# Voltage_Ref.net
KiCad netlist of a schematic drawn in Altium Designer
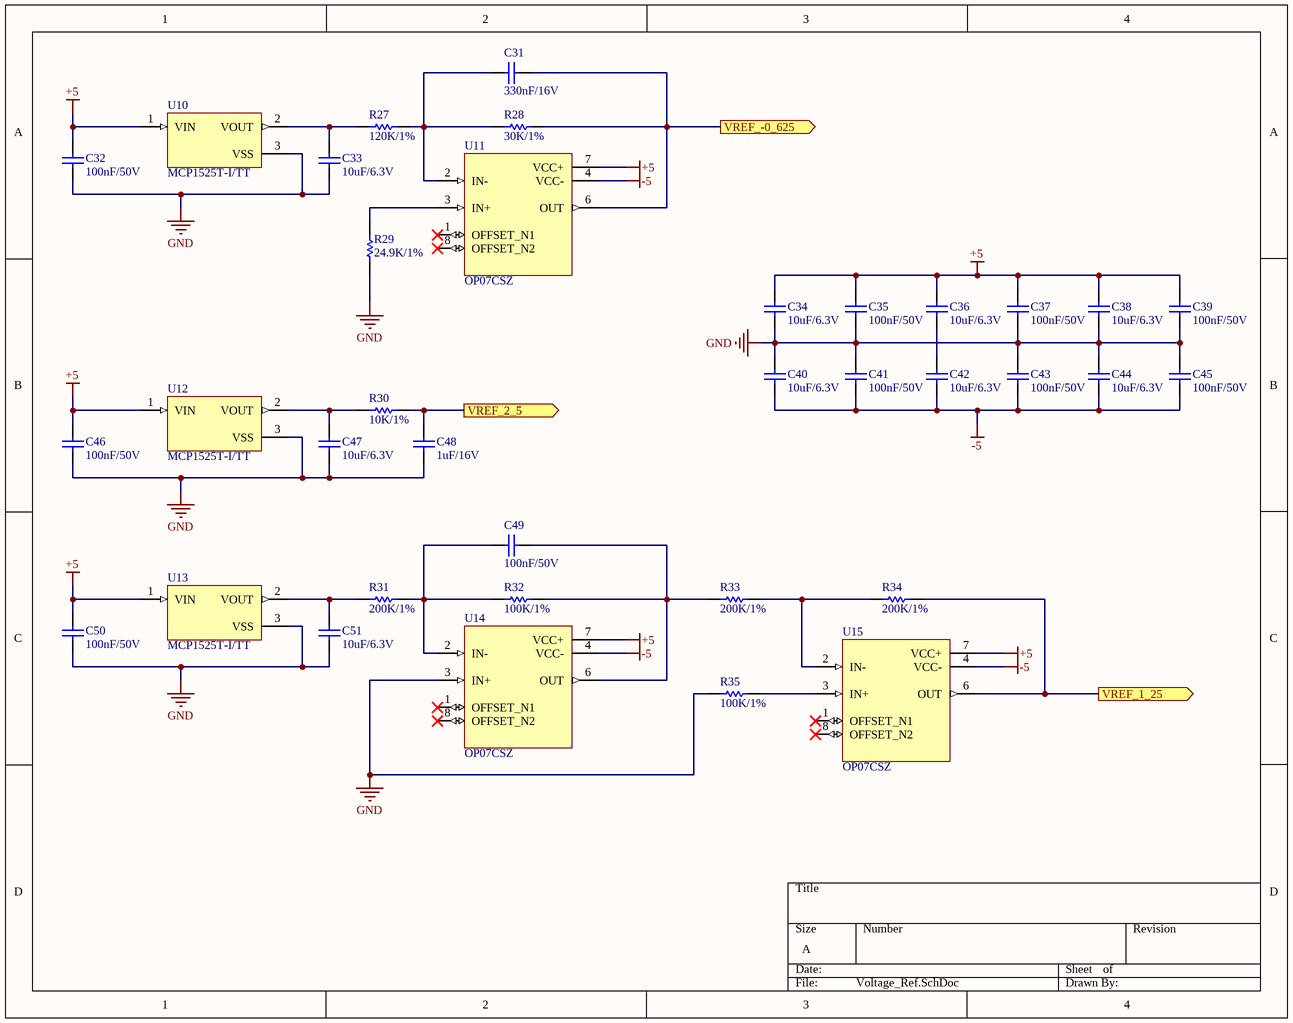
[diagram p0: Voltage_Ref.SchDoc]

(export (version "E")
  (design (tool "Eeschema 10.0.6"))
  (components
    (comp (ref "C31")
      (value "330nF/16V")
      (footprint "CAP_0805")
      (libsource (lib "Iot_Flatform_lib_PTT") (part "Capacitor"))
    )
    (comp (ref "C32")
      (value "100nF/50V")
      (footprint "CAP_0805")
      (libsource (lib "Iot_Flatform_lib_PTT") (part "Capacitor"))
    )
    (comp (ref "C33")
      (value "10uF/6.3V")
      (footprint "CAP_0805")
      (libsource (lib "Iot_Flatform_lib_PTT") (part "Capacitor"))
    )
    (comp (ref "C34")
      (value "10uF/6.3V")
      (footprint "CAP_0805")
      (libsource (lib "Iot_Flatform_lib_PTT") (part "Capacitor"))
    )
    (comp (ref "C35")
      (value "100nF/50V")
      (footprint "CAP_0805")
      (libsource (lib "Iot_Flatform_lib_PTT") (part "Capacitor"))
    )
    (comp (ref "C36")
      (value "10uF/6.3V")
      (footprint "CAP_0805")
      (libsource (lib "Iot_Flatform_lib_PTT") (part "Capacitor"))
    )
    (comp (ref "C37")
      (value "100nF/50V")
      (footprint "CAP_0805")
      (libsource (lib "Iot_Flatform_lib_PTT") (part "Capacitor"))
    )
    (comp (ref "C38")
      (value "10uF/6.3V")
      (footprint "CAP_0805")
      (libsource (lib "Iot_Flatform_lib_PTT") (part "Capacitor"))
    )
    (comp (ref "C39")
      (value "100nF/50V")
      (footprint "CAP_0805")
      (libsource (lib "Iot_Flatform_lib_PTT") (part "Capacitor"))
    )
    (comp (ref "C40")
      (value "10uF/6.3V")
      (footprint "CAP_0805")
      (libsource (lib "Iot_Flatform_lib_PTT") (part "Capacitor"))
    )
    (comp (ref "C41")
      (value "100nF/50V")
      (footprint "CAP_0805")
      (libsource (lib "Iot_Flatform_lib_PTT") (part "Capacitor"))
    )
    (comp (ref "C42")
      (value "10uF/6.3V")
      (footprint "CAP_0805")
      (libsource (lib "Iot_Flatform_lib_PTT") (part "Capacitor"))
    )
    (comp (ref "C43")
      (value "100nF/50V")
      (footprint "CAP_0805")
      (libsource (lib "Iot_Flatform_lib_PTT") (part "Capacitor"))
    )
    (comp (ref "C44")
      (value "10uF/6.3V")
      (footprint "CAP_0805")
      (libsource (lib "Iot_Flatform_lib_PTT") (part "Capacitor"))
    )
    (comp (ref "C45")
      (value "100nF/50V")
      (footprint "CAP_0805")
      (libsource (lib "Iot_Flatform_lib_PTT") (part "Capacitor"))
    )
    (comp (ref "C46")
      (value "100nF/50V")
      (footprint "CAP_0805")
      (libsource (lib "Iot_Flatform_lib_PTT") (part "Capacitor"))
    )
    (comp (ref "C47")
      (value "10uF/6.3V")
      (footprint "CAP_0805")
      (libsource (lib "Iot_Flatform_lib_PTT") (part "Capacitor"))
    )
    (comp (ref "C48")
      (value "1uF/16V")
      (footprint "CAP_0805")
      (libsource (lib "Iot_Flatform_lib_PTT") (part "Capacitor"))
    )
    (comp (ref "C49")
      (value "100nF/50V")
      (footprint "CAP_0805")
      (libsource (lib "Iot_Flatform_lib_PTT") (part "Capacitor"))
    )
    (comp (ref "C50")
      (value "100nF/50V")
      (footprint "CAP_0805")
      (libsource (lib "Iot_Flatform_lib_PTT") (part "Capacitor"))
    )
    (comp (ref "C51")
      (value "10uF/6.3V")
      (footprint "CAP_0805")
      (libsource (lib "Iot_Flatform_lib_PTT") (part "Capacitor"))
    )
    (comp (ref "R27")
      (value "120K/1%")
      (footprint "RES_0805")
      (libsource (lib "Iot_Flatform_lib_PTT") (part "Resistor"))
    )
    (comp (ref "R28")
      (value "30K/1%")
      (footprint "RES_0805")
      (libsource (lib "Iot_Flatform_lib_PTT") (part "Resistor"))
    )
    (comp (ref "R29")
      (value "24.9K/1%")
      (footprint "RES_0805")
      (libsource (lib "Iot_Flatform_lib_PTT") (part "Resistor"))
    )
    (comp (ref "R30")
      (value "10K/1%")
      (footprint "RES_0805")
      (libsource (lib "Iot_Flatform_lib_PTT") (part "Resistor"))
    )
    (comp (ref "R31")
      (value "200K/1%")
      (footprint "RES_0805")
      (libsource (lib "Iot_Flatform_lib_PTT") (part "Resistor"))
    )
    (comp (ref "R32")
      (value "100K/1%")
      (footprint "RES_0805")
      (libsource (lib "Iot_Flatform_lib_PTT") (part "Resistor"))
    )
    (comp (ref "R33")
      (value "200K/1%")
      (footprint "RES_0805")
      (libsource (lib "Iot_Flatform_lib_PTT") (part "Resistor"))
    )
    (comp (ref "R34")
      (value "200K/1%")
      (footprint "RES_0805")
      (libsource (lib "Iot_Flatform_lib_PTT") (part "Resistor"))
    )
    (comp (ref "R35")
      (value "100K/1%")
      (footprint "RES_0805")
      (libsource (lib "Iot_Flatform_lib_PTT") (part "Resistor"))
    )
    (comp (ref "U10")
      (value "MCP1525T-I/TT")
      (footprint "SOT95P237X112-3N")
      (description "Series Voltage Reference IC Â±1% SOT-23-3")
      (libsource (lib "Iot_Flatform_lib_PTT") (part "MCP1525T-I/TT"))
    )
    (comp (ref "U11")
      (value "OP07CSZ")
      (footprint "SOIC127P600X175-8N")
      (description "Low-Offset Voltage Operational Amplifier")
      (libsource (lib "Iot_Flatform_lib_PTT") (part "OP07CSZ"))
    )
    (comp (ref "U12")
      (value "MCP1525T-I/TT")
      (footprint "SOT95P237X112-3N")
      (description "Series Voltage Reference IC Â±1% SOT-23-3")
      (libsource (lib "Iot_Flatform_lib_PTT") (part "MCP1525T-I/TT"))
    )
    (comp (ref "U13")
      (value "MCP1525T-I/TT")
      (footprint "SOT95P237X112-3N")
      (description "Series Voltage Reference IC Â±1% SOT-23-3")
      (libsource (lib "Iot_Flatform_lib_PTT") (part "MCP1525T-I/TT"))
    )
    (comp (ref "U14")
      (value "OP07CSZ")
      (footprint "SOIC127P600X175-8N")
      (description "Low-Offset Voltage Operational Amplifier")
      (libsource (lib "Iot_Flatform_lib_PTT") (part "OP07CSZ"))
    )
    (comp (ref "U15")
      (value "OP07CSZ")
      (footprint "SOIC127P600X175-8N")
      (description "Low-Offset Voltage Operational Amplifier")
      (libsource (lib "Iot_Flatform_lib_PTT") (part "OP07CSZ"))
    )
  )
  (nets
    (net (code "1") (name "+5") (class "Default")
      (node (ref "C32") (pin "2") (pinfunction "2_2") (pintype "passive"))
      (node (ref "C34") (pin "2") (pinfunction "2_2") (pintype "passive"))
      (node (ref "C35") (pin "2") (pinfunction "2_2") (pintype "passive"))
      (node (ref "C36") (pin "2") (pinfunction "2_2") (pintype "passive"))
      (node (ref "C37") (pin "2") (pinfunction "2_2") (pintype "passive"))
      (node (ref "C38") (pin "2") (pinfunction "2_2") (pintype "passive"))
      (node (ref "C39") (pin "2") (pinfunction "2_2") (pintype "passive"))
      (node (ref "C46") (pin "2") (pinfunction "2_2") (pintype "passive"))
      (node (ref "C50") (pin "2") (pinfunction "2_2") (pintype "passive"))
      (node (ref "U10") (pin "1") (pinfunction "VIN_1") (pintype "input"))
      (node (ref "U11") (pin "7") (pinfunction "VCC+_7") (pintype "power_in"))
      (node (ref "U12") (pin "1") (pinfunction "VIN_1") (pintype "input"))
      (node (ref "U13") (pin "1") (pinfunction "VIN_1") (pintype "input"))
      (node (ref "U14") (pin "7") (pinfunction "VCC+_7") (pintype "power_in"))
      (node (ref "U15") (pin "7") (pinfunction "VCC+_7") (pintype "power_in"))
    )
    (net (code "2") (name "-5") (class "Default")
      (node (ref "C40") (pin "1") (pinfunction "1_1") (pintype "passive"))
      (node (ref "C41") (pin "1") (pinfunction "1_1") (pintype "passive"))
      (node (ref "C42") (pin "1") (pinfunction "1_1") (pintype "passive"))
      (node (ref "C43") (pin "1") (pinfunction "1_1") (pintype "passive"))
      (node (ref "C44") (pin "1") (pinfunction "1_1") (pintype "passive"))
      (node (ref "C45") (pin "1") (pinfunction "1_1") (pintype "passive"))
      (node (ref "U11") (pin "4") (pinfunction "VCC-_4") (pintype "power_in"))
      (node (ref "U14") (pin "4") (pinfunction "VCC-_4") (pintype "power_in"))
      (node (ref "U15") (pin "4") (pinfunction "VCC-_4") (pintype "power_in"))
    )
    (net (code "3") (name "/VREF_-0_625") (class "Default")
      (node (ref "C31") (pin "1") (pinfunction "1_1") (pintype "passive"))
      (node (ref "R28") (pin "2") (pinfunction "2_2") (pintype "passive"))
      (node (ref "U11") (pin "6") (pinfunction "OUT_6") (pintype "output"))
    )
    (net (code "4") (name "/VREF_1_25") (class "Default")
      (node (ref "R34") (pin "2") (pinfunction "2_2") (pintype "passive"))
      (node (ref "U15") (pin "6") (pinfunction "OUT_6") (pintype "output"))
    )
    (net (code "5") (name "/VREF_2_5") (class "Default")
      (node (ref "C48") (pin "2") (pinfunction "2_2") (pintype "passive"))
      (node (ref "R30") (pin "1") (pinfunction "1_1") (pintype "passive"))
    )
    (net (code "6") (name "GND") (class "Default")
      (node (ref "C32") (pin "1") (pinfunction "1_1") (pintype "passive"))
      (node (ref "C33") (pin "1") (pinfunction "1_1") (pintype "passive"))
      (node (ref "C34") (pin "1") (pinfunction "1_1") (pintype "passive"))
      (node (ref "C35") (pin "1") (pinfunction "1_1") (pintype "passive"))
      (node (ref "C37") (pin "1") (pinfunction "1_1") (pintype "passive"))
      (node (ref "C38") (pin "1") (pinfunction "1_1") (pintype "passive"))
      (node (ref "C39") (pin "1") (pinfunction "1_1") (pintype "passive"))
      (node (ref "C40") (pin "2") (pinfunction "2_2") (pintype "passive"))
      (node (ref "C41") (pin "2") (pinfunction "2_2") (pintype "passive"))
      (node (ref "C43") (pin "2") (pinfunction "2_2") (pintype "passive"))
      (node (ref "C44") (pin "2") (pinfunction "2_2") (pintype "passive"))
      (node (ref "C45") (pin "2") (pinfunction "2_2") (pintype "passive"))
      (node (ref "C46") (pin "1") (pinfunction "1_1") (pintype "passive"))
      (node (ref "C47") (pin "1") (pinfunction "1_1") (pintype "passive"))
      (node (ref "C48") (pin "1") (pinfunction "1_1") (pintype "passive"))
      (node (ref "C50") (pin "1") (pinfunction "1_1") (pintype "passive"))
      (node (ref "C51") (pin "1") (pinfunction "1_1") (pintype "passive"))
      (node (ref "R29") (pin "1") (pinfunction "1_1") (pintype "passive"))
      (node (ref "R35") (pin "1") (pinfunction "1_1") (pintype "passive"))
      (node (ref "U10") (pin "3") (pinfunction "VSS_3") (pintype "power_in"))
      (node (ref "U12") (pin "3") (pinfunction "VSS_3") (pintype "power_in"))
      (node (ref "U13") (pin "3") (pinfunction "VSS_3") (pintype "power_in"))
      (node (ref "U14") (pin "3") (pinfunction "IN+_3") (pintype "input"))
    )
    (net (code "7") (name "Net-(C36-Pad1)") (class "Default")
      (node (ref "C36") (pin "1") (pinfunction "1_1") (pintype "passive"))
      (node (ref "C42") (pin "2") (pinfunction "2_2") (pintype "passive"))
    )
    (net (code "8") (name "Net-(U10-VOUT)") (class "Default")
      (node (ref "C33") (pin "2") (pinfunction "2_2") (pintype "passive"))
      (node (ref "R27") (pin "1") (pinfunction "1_1") (pintype "passive"))
      (node (ref "U10") (pin "2") (pinfunction "VOUT_2") (pintype "output"))
    )
    (net (code "9") (name "Net-(U11-IN+)") (class "Default")
      (node (ref "R29") (pin "2") (pinfunction "2_2") (pintype "passive"))
      (node (ref "U11") (pin "3") (pinfunction "IN+_3") (pintype "input"))
    )
    (net (code "10") (name "Net-(U11-IN-)") (class "Default")
      (node (ref "C31") (pin "2") (pinfunction "2_2") (pintype "passive"))
      (node (ref "R27") (pin "2") (pinfunction "2_2") (pintype "passive"))
      (node (ref "R28") (pin "1") (pinfunction "1_1") (pintype "passive"))
      (node (ref "U11") (pin "2") (pinfunction "IN-_2") (pintype "input"))
    )
    (net (code "11") (name "Net-(U12-VOUT)") (class "Default")
      (node (ref "C47") (pin "2") (pinfunction "2_2") (pintype "passive"))
      (node (ref "R30") (pin "2") (pinfunction "2_2") (pintype "passive"))
      (node (ref "U12") (pin "2") (pinfunction "VOUT_2") (pintype "output"))
    )
    (net (code "12") (name "Net-(U13-VOUT)") (class "Default")
      (node (ref "C51") (pin "2") (pinfunction "2_2") (pintype "passive"))
      (node (ref "R31") (pin "1") (pinfunction "1_1") (pintype "passive"))
      (node (ref "U13") (pin "2") (pinfunction "VOUT_2") (pintype "output"))
    )
    (net (code "13") (name "Net-(U14-IN-)") (class "Default")
      (node (ref "C49") (pin "2") (pinfunction "2_2") (pintype "passive"))
      (node (ref "R31") (pin "2") (pinfunction "2_2") (pintype "passive"))
      (node (ref "R32") (pin "1") (pinfunction "1_1") (pintype "passive"))
      (node (ref "U14") (pin "2") (pinfunction "IN-_2") (pintype "input"))
    )
    (net (code "14") (name "Net-(U14-OUT)") (class "Default")
      (node (ref "C49") (pin "1") (pinfunction "1_1") (pintype "passive"))
      (node (ref "R32") (pin "2") (pinfunction "2_2") (pintype "passive"))
      (node (ref "R33") (pin "1") (pinfunction "1_1") (pintype "passive"))
      (node (ref "U14") (pin "6") (pinfunction "OUT_6") (pintype "output"))
    )
    (net (code "15") (name "Net-(U15-IN+)") (class "Default")
      (node (ref "R35") (pin "2") (pinfunction "2_2") (pintype "passive"))
      (node (ref "U15") (pin "3") (pinfunction "IN+_3") (pintype "input"))
    )
    (net (code "16") (name "Net-(U15-IN-)") (class "Default")
      (node (ref "R33") (pin "2") (pinfunction "2_2") (pintype "passive"))
      (node (ref "R34") (pin "1") (pinfunction "1_1") (pintype "passive"))
      (node (ref "U15") (pin "2") (pinfunction "IN-_2") (pintype "input"))
    )
    (net (code "17") (name "unconnected-(U11-OFFSET_N1-Pad1)") (class "Default")
      (node (ref "U11") (pin "1") (pinfunction "OFFSET_N1_1") (pintype "bidirectional+no_connect"))
    )
    (net (code "18") (name "unconnected-(U11-OFFSET_N2-Pad8)") (class "Default")
      (node (ref "U11") (pin "8") (pinfunction "OFFSET_N2_8") (pintype "bidirectional+no_connect"))
    )
    (net (code "19") (name "unconnected-(U14-OFFSET_N1-Pad1)") (class "Default")
      (node (ref "U14") (pin "1") (pinfunction "OFFSET_N1_1") (pintype "bidirectional+no_connect"))
    )
    (net (code "20") (name "unconnected-(U14-OFFSET_N2-Pad8)") (class "Default")
      (node (ref "U14") (pin "8") (pinfunction "OFFSET_N2_8") (pintype "bidirectional+no_connect"))
    )
    (net (code "21") (name "unconnected-(U15-OFFSET_N1-Pad1)") (class "Default")
      (node (ref "U15") (pin "1") (pinfunction "OFFSET_N1_1") (pintype "bidirectional+no_connect"))
    )
    (net (code "22") (name "unconnected-(U15-OFFSET_N2-Pad8)") (class "Default")
      (node (ref "U15") (pin "8") (pinfunction "OFFSET_N2_8") (pintype "bidirectional+no_connect"))
    )
  )
)
